# ProPrj_EMU_Button_PCB_rev1_2.net
KiCad netlist of a schematic drawn in EasyEDA Pro
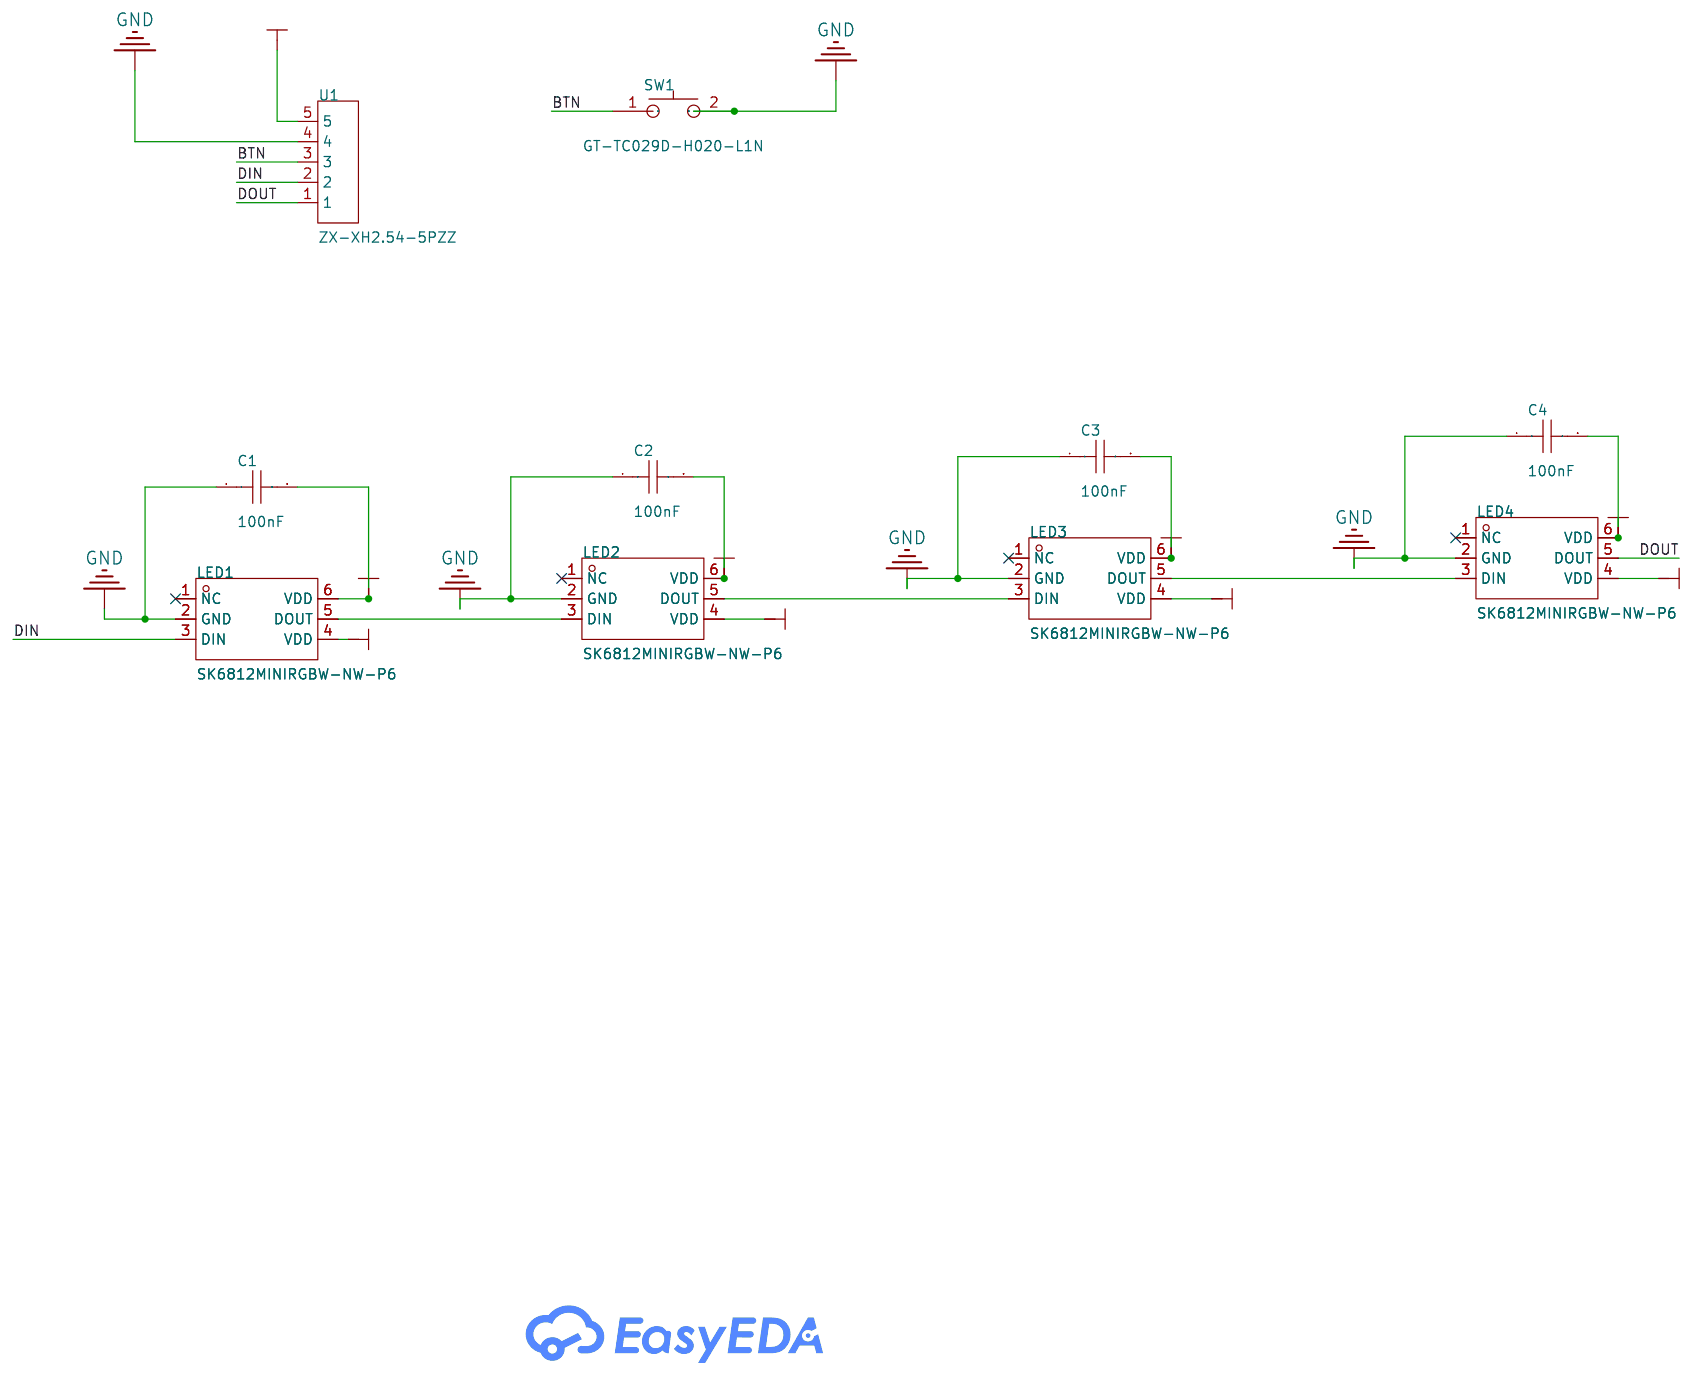
[diagram p0: schematic sheet]

(export (version "E")
  (design (tool "Eeschema 10.0.6"))
  (components
    (comp (ref "C1")
      (value "100nF")
      (footprint "easyedapro:C0603")
      (description "Capacitance:100nF Tolerance:±10% Tolerance:±10% Voltage Rating:50V Temperature Coefficient:X7R")
      (fields
        (field (name "Manufacturer Part") "CC0603KRX7R9BB104")
        (field (name "Manufacturer") "YAGEO(国巨)")
      )
      (libsource (lib "easyedapro") (part "CC0603KRX7R9BB104"))
    )
    (comp (ref "C2")
      (value "100nF")
      (footprint "easyedapro:C0603")
      (description "Capacitance:100nF Tolerance:±10% Tolerance:±10% Voltage Rating:50V Temperature Coefficient:X7R")
      (fields
        (field (name "Manufacturer Part") "CC0603KRX7R9BB104")
        (field (name "Manufacturer") "YAGEO(国巨)")
      )
      (libsource (lib "easyedapro") (part "CC0603KRX7R9BB104"))
    )
    (comp (ref "C3")
      (value "100nF")
      (footprint "easyedapro:C0603")
      (description "Capacitance:100nF Tolerance:±10% Tolerance:±10% Voltage Rating:50V Temperature Coefficient:X7R")
      (fields
        (field (name "Manufacturer Part") "CC0603KRX7R9BB104")
        (field (name "Manufacturer") "YAGEO(国巨)")
      )
      (libsource (lib "easyedapro") (part "CC0603KRX7R9BB104"))
    )
    (comp (ref "C4")
      (value "100nF")
      (footprint "easyedapro:C0603")
      (description "Capacitance:100nF Tolerance:±10% Tolerance:±10% Voltage Rating:50V Temperature Coefficient:X7R")
      (fields
        (field (name "Manufacturer Part") "CC0603KRX7R9BB104")
        (field (name "Manufacturer") "YAGEO(国巨)")
      )
      (libsource (lib "easyedapro") (part "CC0603KRX7R9BB104"))
    )
    (comp (ref "LED1")
      (value "SK6812MINIRGBW-NW-P6")
      (footprint "easyedapro:LED-ARRAY-SMD_6P-L3.7-W3.5-TL-RD-1")
      (fields (field (name "Manufacturer") "欧思科光电"))
      (libsource (lib "easyedapro") (part "SK6812MINIRGBW-NW-P6"))
    )
    (comp (ref "LED2")
      (value "SK6812MINIRGBW-NW-P6")
      (footprint "easyedapro:LED-ARRAY-SMD_6P-L3.7-W3.5-TL-RD-1")
      (fields (field (name "Manufacturer") "欧思科光电"))
      (libsource (lib "easyedapro") (part "SK6812MINIRGBW-NW-P6"))
    )
    (comp (ref "LED3")
      (value "SK6812MINIRGBW-NW-P6")
      (footprint "easyedapro:LED-ARRAY-SMD_6P-L3.7-W3.5-TL-RD-1")
      (fields (field (name "Manufacturer") "欧思科光电"))
      (libsource (lib "easyedapro") (part "SK6812MINIRGBW-NW-P6"))
    )
    (comp (ref "LED4")
      (value "SK6812MINIRGBW-NW-P6")
      (footprint "easyedapro:LED-ARRAY-SMD_6P-L3.7-W3.5-TL-RD-1")
      (fields (field (name "Manufacturer") "欧思科光电"))
      (libsource (lib "easyedapro") (part "SK6812MINIRGBW-NW-P6"))
    )
    (comp (ref "SW1")
      (value "GT-TC029D-H020-L1N")
      (footprint "easyedapro:SW-SMD_L3.9-W2.9-LS4.8")
      (fields (field (name "Manufacturer") "G-Switch(品赞)"))
      (libsource (lib "easyedapro") (part "GT-TC029D-H020-L1"))
    )
    (comp (ref "U1")
      (value "ZX-XH2.54-5PZZ")
      (footprint "easyedapro:CONN-TH_5P-P2.50_ZX-XH2.54-5PZZ")
      (fields (field (name "Manufacturer") "Megastar(兆星)"))
      (libsource (lib "easyedapro") (part "ZX-XH2.54-5PZZ"))
    )
  )
  (nets
    (net (code "1") (name "/BTN") (class "Default")
      (node (ref "SW1") (pin "1") (pinfunction "1_1") (pintype "unspecified"))
      (node (ref "U1") (pin "3") (pinfunction "3_3") (pintype "unspecified"))
    )
    (net (code "2") (name "/DIN") (class "Default")
      (node (ref "LED1") (pin "3") (pinfunction "DIN_3") (pintype "unspecified"))
      (node (ref "U1") (pin "2") (pinfunction "2_2") (pintype "unspecified"))
    )
    (net (code "3") (name "/DOUT") (class "Default")
      (node (ref "LED4") (pin "5") (pinfunction "DOUT_5") (pintype "unspecified"))
      (node (ref "U1") (pin "1") (pinfunction "1_1") (pintype "unspecified"))
    )
    (net (code "4") (name "GND") (class "Default")
      (node (ref "C1") (pin "1") (pinfunction "1_1") (pintype "unspecified"))
      (node (ref "C2") (pin "1") (pinfunction "1_1") (pintype "unspecified"))
      (node (ref "C3") (pin "1") (pinfunction "1_1") (pintype "unspecified"))
      (node (ref "C4") (pin "1") (pinfunction "1_1") (pintype "unspecified"))
      (node (ref "LED1") (pin "2") (pinfunction "GND_2") (pintype "unspecified"))
      (node (ref "LED2") (pin "2") (pinfunction "GND_2") (pintype "unspecified"))
      (node (ref "LED3") (pin "2") (pinfunction "GND_2") (pintype "unspecified"))
      (node (ref "LED4") (pin "2") (pinfunction "GND_2") (pintype "unspecified"))
      (node (ref "SW1") (pin "2") (pinfunction "2_2") (pintype "unspecified"))
      (node (ref "U1") (pin "4") (pinfunction "4_4") (pintype "unspecified"))
    )
    (net (code "5") (name "Net-(LED1-DOUT)") (class "Default")
      (node (ref "LED1") (pin "5") (pinfunction "DOUT_5") (pintype "unspecified"))
      (node (ref "LED2") (pin "3") (pinfunction "DIN_3") (pintype "unspecified"))
    )
    (net (code "6") (name "Net-(LED2-DOUT)") (class "Default")
      (node (ref "LED2") (pin "5") (pinfunction "DOUT_5") (pintype "unspecified"))
      (node (ref "LED3") (pin "3") (pinfunction "DIN_3") (pintype "unspecified"))
    )
    (net (code "7") (name "Net-(LED3-DOUT)") (class "Default")
      (node (ref "LED3") (pin "5") (pinfunction "DOUT_5") (pintype "unspecified"))
      (node (ref "LED4") (pin "3") (pinfunction "DIN_3") (pintype "unspecified"))
    )
    (net (code "8") (name "VCC") (class "Default")
      (node (ref "C1") (pin "2") (pinfunction "2_2") (pintype "unspecified"))
      (node (ref "C2") (pin "2") (pinfunction "2_2") (pintype "unspecified"))
      (node (ref "C3") (pin "2") (pinfunction "2_2") (pintype "unspecified"))
      (node (ref "C4") (pin "2") (pinfunction "2_2") (pintype "unspecified"))
      (node (ref "LED1") (pin "4") (pinfunction "VDD_4") (pintype "unspecified"))
      (node (ref "LED1") (pin "6") (pinfunction "VDD_6") (pintype "unspecified"))
      (node (ref "LED2") (pin "4") (pinfunction "VDD_4") (pintype "unspecified"))
      (node (ref "LED2") (pin "6") (pinfunction "VDD_6") (pintype "unspecified"))
      (node (ref "LED3") (pin "4") (pinfunction "VDD_4") (pintype "unspecified"))
      (node (ref "LED3") (pin "6") (pinfunction "VDD_6") (pintype "unspecified"))
      (node (ref "LED4") (pin "4") (pinfunction "VDD_4") (pintype "unspecified"))
      (node (ref "LED4") (pin "6") (pinfunction "VDD_6") (pintype "unspecified"))
      (node (ref "U1") (pin "5") (pinfunction "5_5") (pintype "unspecified"))
    )
    (net (code "9") (name "unconnected-(LED1-NC-Pad1)") (class "Default")
      (node (ref "LED1") (pin "1") (pinfunction "NC_1") (pintype "unspecified+no_connect"))
    )
    (net (code "10") (name "unconnected-(LED2-NC-Pad1)") (class "Default")
      (node (ref "LED2") (pin "1") (pinfunction "NC_1") (pintype "unspecified+no_connect"))
    )
    (net (code "11") (name "unconnected-(LED3-NC-Pad1)") (class "Default")
      (node (ref "LED3") (pin "1") (pinfunction "NC_1") (pintype "unspecified+no_connect"))
    )
    (net (code "12") (name "unconnected-(LED4-NC-Pad1)") (class "Default")
      (node (ref "LED4") (pin "1") (pinfunction "NC_1") (pintype "unspecified+no_connect"))
    )
  )
)
